# BareMetalArduino.net
KiCad netlist of a schematic drawn in EAGLE
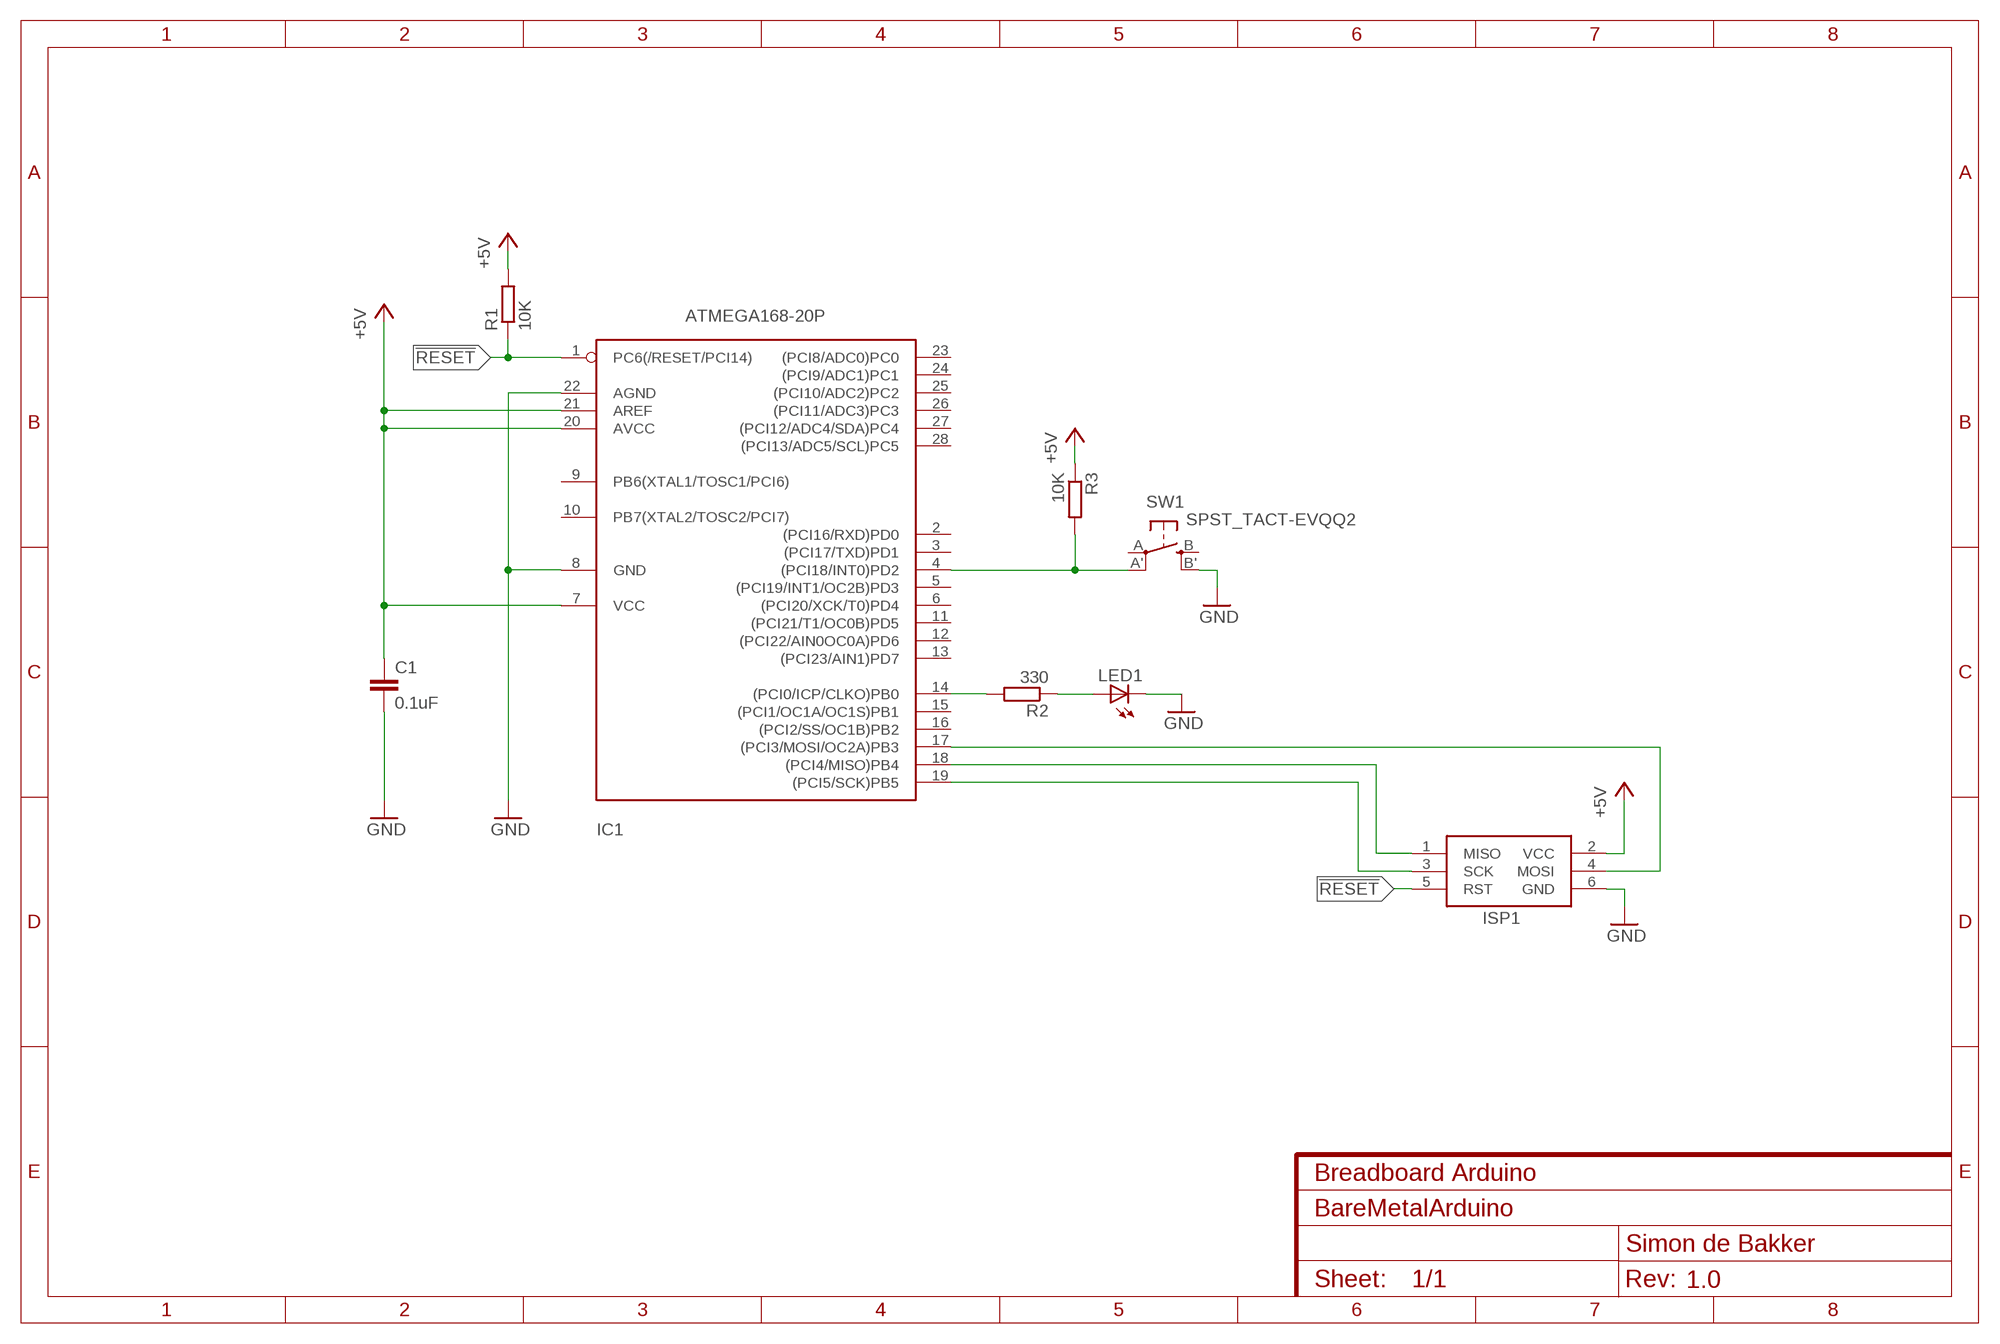
[diagram p0: schematic, sheet 1]

(export (version "E")
  (design (tool "Eeschema 10.0.6"))
  (components
    (comp (ref "C1")
      (value "0.1uF")
      (footprint "eagle-import:C050-024X044")
      (libsource (lib "eagle-import") (part "C-EU050-024X044"))
    )
    (comp (ref "IC1")
      (value "ATMEGA168-20P")
      (footprint "eagle-import:DIL28-3")
      (libsource (lib "eagle-import") (part "ATMEGA168P-20"))
    )
    (comp (ref "ISP1")
      (value "AVRISP-6")
      (footprint "eagle-import:AVRISP")
      (libsource (lib "eagle-import") (part "AVRISP-6"))
    )
    (comp (ref "LED1")
      (value "LED5MM")
      (footprint "eagle-import:LED5MM")
      (libsource (lib "eagle-import") (part "LED5MM"))
    )
    (comp (ref "R1")
      (value "10K")
      (footprint "eagle-import:0207_15")
      (libsource (lib "eagle-import") (part "R-EU_0207/15"))
    )
    (comp (ref "R2")
      (value "330")
      (footprint "eagle-import:0207_15")
      (libsource (lib "eagle-import") (part "R-EU_0207/15"))
    )
    (comp (ref "R3")
      (value "10K")
      (footprint "eagle-import:0207_15")
      (libsource (lib "eagle-import") (part "R-EU_0207/15"))
    )
    (comp (ref "SW1")
      (value "SPST_TACT-EVQQ2")
      (footprint "eagle-import:EVQ-Q2")
      (libsource (lib "eagle-import") (part "SPST_TACT-EVQQ2"))
    )
  )
  (nets
    (net (code "1") (name "+5V") (class "Default")
      (node (ref "C1") (pin "1") (pinfunction "1_1") (pintype "passive"))
      (node (ref "IC1") (pin "20") (pinfunction "AVCC_20") (pintype "bidirectional"))
      (node (ref "IC1") (pin "21") (pinfunction "AREF_21") (pintype "bidirectional"))
      (node (ref "IC1") (pin "7") (pinfunction "VCC_7") (pintype "bidirectional"))
      (node (ref "ISP1") (pin "2") (pinfunction "VCC_2") (pintype "power_in"))
      (node (ref "R1") (pin "2") (pinfunction "2_2") (pintype "passive"))
      (node (ref "R3") (pin "1") (pinfunction "1_1") (pintype "passive"))
    )
    (net (code "2") (name "/~{RESET}") (class "Default")
      (node (ref "IC1") (pin "1") (pinfunction "PC6(/RESET/PCI14)_1") (pintype "bidirectional"))
      (node (ref "ISP1") (pin "5") (pinfunction "RST_5") (pintype "output"))
      (node (ref "R1") (pin "1") (pinfunction "1_1") (pintype "passive"))
    )
    (net (code "3") (name "GND") (class "Default")
      (node (ref "C1") (pin "2") (pinfunction "2_2") (pintype "passive"))
      (node (ref "IC1") (pin "22") (pinfunction "AGND_22") (pintype "bidirectional"))
      (node (ref "IC1") (pin "8") (pinfunction "GND_8") (pintype "bidirectional"))
      (node (ref "ISP1") (pin "6") (pinfunction "GND_6") (pintype "power_in"))
      (node (ref "LED1") (pin "K") (pinfunction "C_K") (pintype "passive"))
      (node (ref "SW1") (pin "B'") (pinfunction "S1_B'") (pintype "passive"))
    )
    (net (code "4") (name "Net-(IC1-(PCI0{slash}ICP{slash}CLKO)PB0)") (class "Default")
      (node (ref "IC1") (pin "14") (pinfunction "(PCI0/ICP/CLKO)PB0_14") (pintype "bidirectional"))
      (node (ref "R2") (pin "2") (pinfunction "2_2") (pintype "passive"))
    )
    (net (code "5") (name "Net-(IC1-(PCI3{slash}MOSI{slash}OC2A)PB3)") (class "Default")
      (node (ref "IC1") (pin "17") (pinfunction "(PCI3/MOSI/OC2A)PB3_17") (pintype "bidirectional"))
      (node (ref "ISP1") (pin "4") (pinfunction "MOSI_4") (pintype "output"))
    )
    (net (code "6") (name "Net-(IC1-(PCI4{slash}MISO)PB4)") (class "Default")
      (node (ref "IC1") (pin "18") (pinfunction "(PCI4/MISO)PB4_18") (pintype "bidirectional"))
      (node (ref "ISP1") (pin "1") (pinfunction "MISO_1") (pintype "input"))
    )
    (net (code "7") (name "Net-(IC1-(PCI5{slash}SCK)PB5)") (class "Default")
      (node (ref "IC1") (pin "19") (pinfunction "(PCI5/SCK)PB5_19") (pintype "bidirectional"))
      (node (ref "ISP1") (pin "3") (pinfunction "SCK_3") (pintype "output"))
    )
    (net (code "8") (name "Net-(IC1-(PCI18{slash}INT0)PD2)") (class "Default")
      (node (ref "IC1") (pin "4") (pinfunction "(PCI18/INT0)PD2_4") (pintype "bidirectional"))
      (node (ref "R3") (pin "2") (pinfunction "2_2") (pintype "passive"))
      (node (ref "SW1") (pin "A'") (pinfunction "P1_A'") (pintype "passive"))
    )
    (net (code "9") (name "Net-(LED1-PadA)") (class "Default")
      (node (ref "LED1") (pin "A") (pinfunction "A_A") (pintype "passive"))
      (node (ref "R2") (pin "1") (pinfunction "1_1") (pintype "passive"))
    )
    (net (code "10") (name "unconnected-(IC1-(PCI1{slash}OC1A{slash}OC1S)PB1-Pad15)") (class "Default")
      (node (ref "IC1") (pin "15") (pinfunction "(PCI1/OC1A/OC1S)PB1_15") (pintype "bidirectional"))
    )
    (net (code "11") (name "unconnected-(IC1-(PCI2{slash}SS{slash}OC1B)PB2-Pad16)") (class "Default")
      (node (ref "IC1") (pin "16") (pinfunction "(PCI2/SS/OC1B)PB2_16") (pintype "bidirectional"))
    )
    (net (code "12") (name "unconnected-(IC1-(PCI8{slash}ADC0)PC0-Pad23)") (class "Default")
      (node (ref "IC1") (pin "23") (pinfunction "(PCI8/ADC0)PC0_23") (pintype "bidirectional"))
    )
    (net (code "13") (name "unconnected-(IC1-(PCI9{slash}ADC1)PC1-Pad24)") (class "Default")
      (node (ref "IC1") (pin "24") (pinfunction "(PCI9/ADC1)PC1_24") (pintype "bidirectional"))
    )
    (net (code "14") (name "unconnected-(IC1-(PCI10{slash}ADC2)PC2-Pad25)") (class "Default")
      (node (ref "IC1") (pin "25") (pinfunction "(PCI10/ADC2)PC2_25") (pintype "bidirectional"))
    )
    (net (code "15") (name "unconnected-(IC1-(PCI11{slash}ADC3)PC3-Pad26)") (class "Default")
      (node (ref "IC1") (pin "26") (pinfunction "(PCI11/ADC3)PC3_26") (pintype "bidirectional"))
    )
    (net (code "16") (name "unconnected-(IC1-(PCI12{slash}ADC4{slash}SDA)PC4-Pad27)") (class "Default")
      (node (ref "IC1") (pin "27") (pinfunction "(PCI12/ADC4/SDA)PC4_27") (pintype "bidirectional"))
    )
    (net (code "17") (name "unconnected-(IC1-(PCI13{slash}ADC5{slash}SCL)PC5-Pad28)") (class "Default")
      (node (ref "IC1") (pin "28") (pinfunction "(PCI13/ADC5/SCL)PC5_28") (pintype "bidirectional"))
    )
    (net (code "18") (name "unconnected-(IC1-(PCI16{slash}RXD)PD0-Pad2)") (class "Default")
      (node (ref "IC1") (pin "2") (pinfunction "(PCI16/RXD)PD0_2") (pintype "bidirectional"))
    )
    (net (code "19") (name "unconnected-(IC1-(PCI17{slash}TXD)PD1-Pad3)") (class "Default")
      (node (ref "IC1") (pin "3") (pinfunction "(PCI17/TXD)PD1_3") (pintype "bidirectional"))
    )
    (net (code "20") (name "unconnected-(IC1-(PCI19{slash}INT1{slash}OC2B)PD3-Pad5)") (class "Default")
      (node (ref "IC1") (pin "5") (pinfunction "(PCI19/INT1/OC2B)PD3_5") (pintype "bidirectional"))
    )
    (net (code "21") (name "unconnected-(IC1-(PCI20{slash}XCK{slash}T0)PD4-Pad6)") (class "Default")
      (node (ref "IC1") (pin "6") (pinfunction "(PCI20/XCK/T0)PD4_6") (pintype "bidirectional"))
    )
    (net (code "22") (name "unconnected-(IC1-(PCI21{slash}T1{slash}OC0B)PD5-Pad11)") (class "Default")
      (node (ref "IC1") (pin "11") (pinfunction "(PCI21/T1/OC0B)PD5_11") (pintype "bidirectional"))
    )
    (net (code "23") (name "unconnected-(IC1-(PCI22{slash}AIN0OC0A)PD6-Pad12)") (class "Default")
      (node (ref "IC1") (pin "12") (pinfunction "(PCI22/AIN0OC0A)PD6_12") (pintype "bidirectional"))
    )
    (net (code "24") (name "unconnected-(IC1-(PCI23{slash}AIN1)PD7-Pad13)") (class "Default")
      (node (ref "IC1") (pin "13") (pinfunction "(PCI23/AIN1)PD7_13") (pintype "bidirectional"))
    )
    (net (code "25") (name "unconnected-(IC1-PB6(XTAL1{slash}TOSC1{slash}PCI6)-Pad9)") (class "Default")
      (node (ref "IC1") (pin "9") (pinfunction "PB6(XTAL1/TOSC1/PCI6)_9") (pintype "bidirectional"))
    )
    (net (code "26") (name "unconnected-(IC1-PB7(XTAL2{slash}TOSC2{slash}PCI7)-Pad10)") (class "Default")
      (node (ref "IC1") (pin "10") (pinfunction "PB7(XTAL2/TOSC2/PCI7)_10") (pintype "bidirectional"))
    )
    (net (code "27") (name "unconnected-(SW1-P-PadA)") (class "Default")
      (node (ref "SW1") (pin "A") (pinfunction "P_A") (pintype "passive"))
    )
    (net (code "28") (name "unconnected-(SW1-S-PadB)") (class "Default")
      (node (ref "SW1") (pin "B") (pinfunction "S_B") (pintype "passive"))
    )
  )
)
